# 3_mcu.net
KiCad netlist of a schematic drawn in Altium Designer
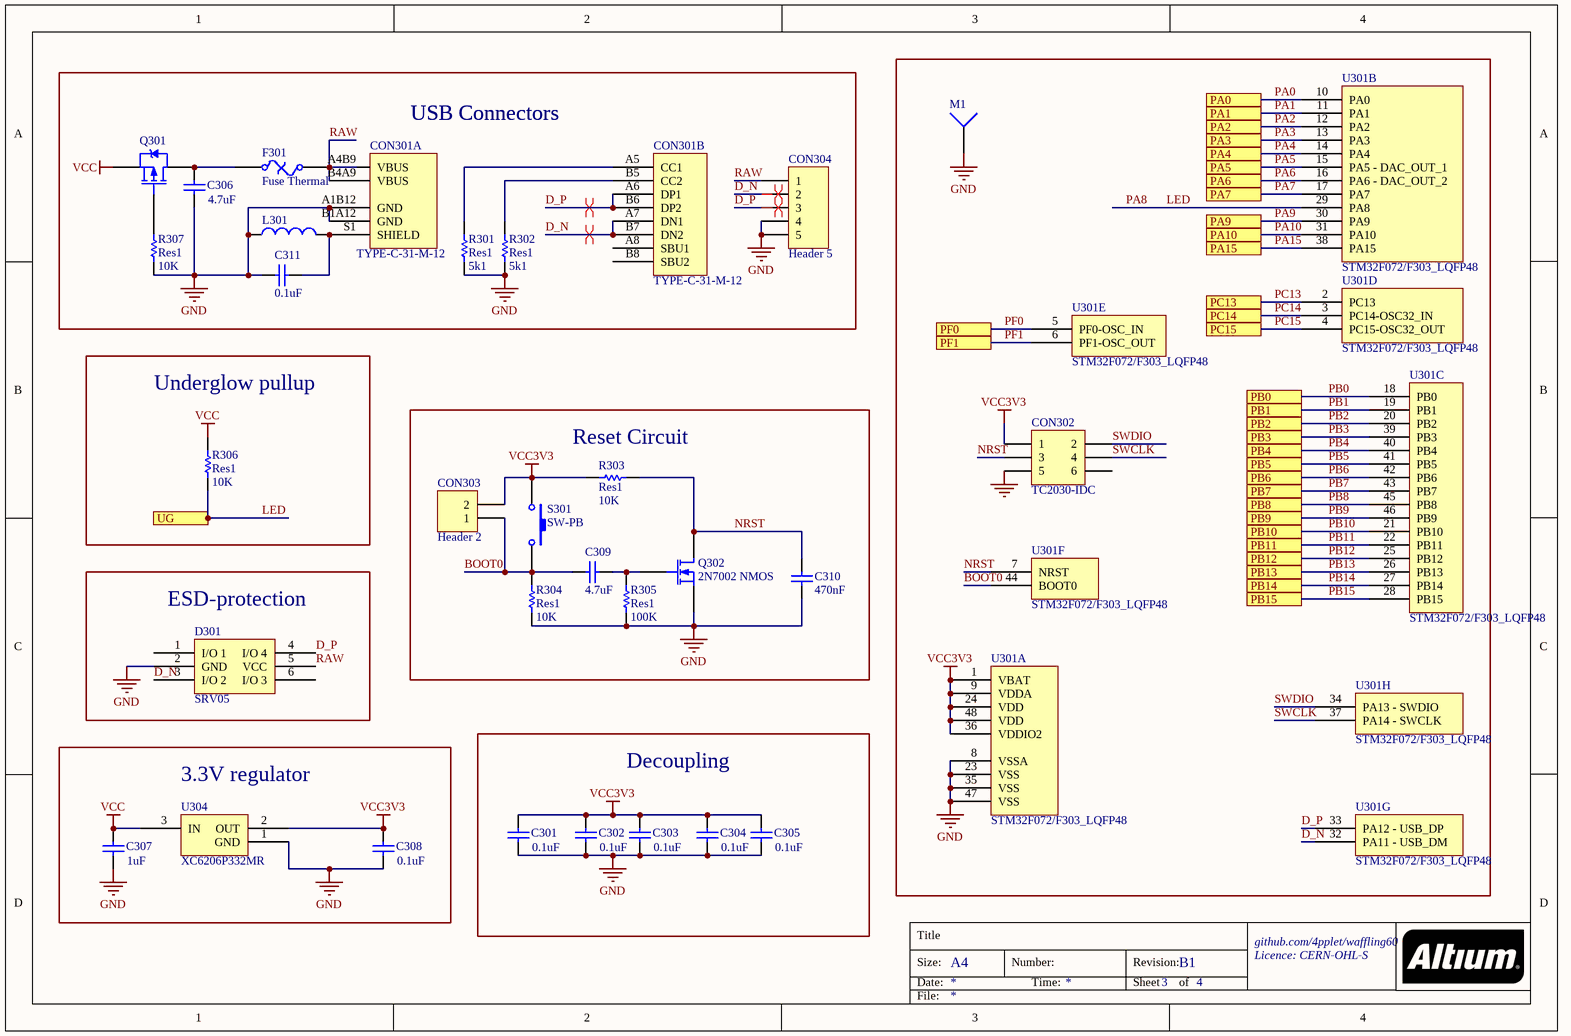
[diagram p0: 3_mcu.SchDoc]

(export (version "E")
  (design (tool "Eeschema 10.0.6"))
  (components
    (comp (ref "C301")
      (value "0.1uF")
      (footprint "C0603[1608]")
      (description "Capacitor")
      (fields (field (name "LCSC PART #") "C14663") (field (name "MRF.PART") "CC0603KRX7R9BB104"))
      (libsource (lib "Miscellaneous Devices") (part "Cap"))
    )
    (comp (ref "C302")
      (value "0.1uF")
      (footprint "C0603[1608]")
      (description "Capacitor")
      (fields (field (name "LCSC PART #") "C14663") (field (name "MRF.PART") "CC0603KRX7R9BB104"))
      (libsource (lib "Miscellaneous Devices") (part "Cap"))
    )
    (comp (ref "C303")
      (value "0.1uF")
      (footprint "C0603[1608]")
      (description "Capacitor")
      (fields (field (name "LCSC PART #") "C14663") (field (name "MRF.PART") "CC0603KRX7R9BB104"))
      (libsource (lib "Miscellaneous Devices") (part "Cap"))
    )
    (comp (ref "C304")
      (value "0.1uF")
      (footprint "C0603[1608]")
      (description "Capacitor")
      (fields (field (name "LCSC PART #") "C14663") (field (name "MRF.PART") "CC0603KRX7R9BB104"))
      (libsource (lib "Miscellaneous Devices") (part "Cap"))
    )
    (comp (ref "C305")
      (value "0.1uF")
      (footprint "C0603[1608]")
      (description "Capacitor")
      (fields (field (name "LCSC PART #") "C14663") (field (name "MRF.PART") "CC0603KRX7R9BB104"))
      (libsource (lib "Miscellaneous Devices") (part "Cap"))
    )
    (comp (ref "C306")
      (value "4.7uF")
      (footprint "C0603[1608]")
      (description "Capacitor")
      (fields (field (name "LCSC PART #") "C19666") (field (name "MRF.PART") "CL10A475KO8NNNC"))
      (libsource (lib "Miscellaneous Devices") (part "Cap"))
    )
    (comp (ref "C307")
      (value "1uF")
      (footprint "C0603[1608]")
      (description "Capacitor")
      (fields (field (name "LCSC PART #") "C15849") (field (name "MRF.PART") "CL10A105KB8NNNC"))
      (libsource (lib "Miscellaneous Devices") (part "Cap"))
    )
    (comp (ref "C308")
      (value "0.1uF")
      (footprint "C0603[1608]")
      (description "Capacitor")
      (fields (field (name "LCSC PART #") "C14663") (field (name "MRF.PART") "CC0603KRX7R9BB104"))
      (libsource (lib "Miscellaneous Devices") (part "Cap"))
    )
    (comp (ref "C309")
      (value "4.7uF")
      (footprint "C0603[1608]")
      (description "Capacitor")
      (fields (field (name "LCSC PART #") "C19666") (field (name "MRF.PART") "CL10A475KO8NNNC"))
      (libsource (lib "Miscellaneous Devices") (part "Cap"))
    )
    (comp (ref "C310")
      (value "470nF")
      (footprint "C0603[1608]")
      (description "Capacitor")
      (fields (field (name "LCSC PART #") "C1623") (field (name "MRF.PART") "CL10B474KA8NNNC"))
      (libsource (lib "Miscellaneous Devices") (part "Cap"))
    )
    (comp (ref "C311")
      (value "0.1uF")
      (footprint "C0603[1608]")
      (description "Capacitor")
      (fields (field (name "LCSC PART #") "C14663") (field (name "MRF.PART") "CC0603KRX7R9BB104"))
      (libsource (lib "Miscellaneous Devices") (part "Cap"))
    )
    (comp (ref "CON301")
      (value "TYPE-C-31-M-12")
      (footprint "TYPE-C-31-M-12")
      (fields (field (name "LCSC PART #") "C165948"))
      (libsource (lib "Schlib1") (part "TYPE-C-31-M-12"))
    )
    (comp (ref "CON302")
      (value "TC2030-IDC")
      (footprint "TC2030-IDC-NL")
      (description "Header, 3-Pin, Dual row")
      (libsource (lib "Miscellaneous Connectors") (part "Header 3X2"))
    )
    (comp (ref "CON303")
      (value "Header 2")
      (footprint "HDR1X2")
      (description "Header, 2-Pin")
      (libsource (lib "Miscellaneous Connectors") (part "Header 2"))
    )
    (comp (ref "CON304")
      (value "Header 5")
      (footprint "JST SM04B-SRSS-TB")
      (description "JST for USB daughter board")
      (fields (field (name "LCSC PART #") "C160404") (field (name "MRF.PART") "SM04B-SRSS-TB(LF)(SN)"))
      (libsource (lib "Miscellaneous Connectors") (part "Header 5"))
    )
    (comp (ref "D301")
      (value "SRV05")
      (footprint "SOT-23-6")
      (fields (field (name "LCSC PART #") "C85364") (field (name "MRF.PART") "SRV05-4-P-T7"))
      (libsource (lib "Keebs") (part "SRV05"))
    )
    (comp (ref "F301")
      (value "Fuse Thermal")
      (footprint "C1206[3216]")
      (description "Thermal Fuse")
      (fields (field (name "LCSC PART #") "C135338") (field (name "MRF.PART") "ASMD1206-050"))
      (libsource (lib "Miscellaneous Devices") (part "Fuse Thermal"))
    )
    (comp (ref "L301")
      (value "Inductor")
      (footprint "L0805")
      (fields (field (name "LCSC PART #") "C1015") (field (name "MRF.PART") "GZ2012D101TF"))
      (libsource (lib "Simulation Generic Components") (part "Inductor"))
    )
    (comp (ref "M1")
      (value "Socket")
      (footprint "mounting_hole")
      (libsource (lib "Miscellaneous Connectors") (part "Socket"))
    )
    (comp (ref "Q301")
      (value "PMOS-2")
      (footprint "SOT-23-3")
      (description "P-Channel Power MOSFET")
      (fields (field (name "LCSC PART #") "C10487") (field (name "MRF.PART") "SI2301CDS-T1-GE3"))
      (libsource (lib "Miscellaneous Devices") (part "PMOS-2"))
    )
    (comp (ref "Q302")
      (value "2N7002 NMOS")
      (footprint "SOT-23-3")
      (description "N-Channel MOSFET")
      (fields (field (name "LCSC PART #") "C8545") (field (name "MRF.PART") "2N7002"))
      (libsource (lib "Miscellaneous Devices") (part "MOSFET-N"))
    )
    (comp (ref "R301")
      (value "Res1")
      (footprint "R0603[1608]")
      (description "Resistor")
      (fields
        (field (name "ALTIUM_VALUE") "5k1")
        (field (name "LCSC PART #") "C23186")
        (field (name "MRF.PART") "0603WAF5101T5E")
      )
      (libsource (lib "Miscellaneous Devices") (part "Res1"))
    )
    (comp (ref "R302")
      (value "Res1")
      (footprint "R0603[1608]")
      (description "Resistor")
      (fields
        (field (name "ALTIUM_VALUE") "5k1")
        (field (name "LCSC PART #") "C23186")
        (field (name "MRF.PART") "0603WAF5101T5E")
      )
      (libsource (lib "Miscellaneous Devices") (part "Res1"))
    )
    (comp (ref "R303")
      (value "Res1")
      (footprint "R0603[1608]")
      (description "Resistor")
      (fields
        (field (name "ALTIUM_VALUE") "10K")
        (field (name "LCSC PART #") "C25804")
        (field (name "MRF.PART") "0603WAF1002T5E")
      )
      (libsource (lib "Miscellaneous Devices") (part "Res1"))
    )
    (comp (ref "R304")
      (value "Res1")
      (footprint "R0603[1608]")
      (description "Resistor")
      (fields
        (field (name "ALTIUM_VALUE") "10K")
        (field (name "LCSC PART #") "C25804")
        (field (name "MRF.PART") "0603WAF1002T5E")
      )
      (libsource (lib "Miscellaneous Devices") (part "Res1"))
    )
    (comp (ref "R305")
      (value "Res1")
      (footprint "R0603[1608]")
      (description "Resistor")
      (fields
        (field (name "ALTIUM_VALUE") "100K")
        (field (name "LCSC PART #") "C25803")
        (field (name "MRF.PART") "0603WAF1003T5E")
      )
      (libsource (lib "Miscellaneous Devices") (part "Res1"))
    )
    (comp (ref "R306")
      (value "Res1")
      (footprint "R0603[1608]")
      (description "Resistor")
      (fields
        (field (name "ALTIUM_VALUE") "10K")
        (field (name "LCSC PART #") "C25804")
        (field (name "MRF.PART") "0603WAF1002T5E")
      )
      (libsource (lib "Miscellaneous Devices") (part "Res1"))
    )
    (comp (ref "R307")
      (value "Res1")
      (footprint "R0603[1608]")
      (description "Resistor")
      (fields
        (field (name "ALTIUM_VALUE") "10K")
        (field (name "LCSC PART #") "C25804")
        (field (name "MRF.PART") "0603WAF1002T5E")
      )
      (libsource (lib "Miscellaneous Devices") (part "Res1"))
    )
    (comp (ref "S301")
      (value "SW-PB")
      (footprint "XKB Switch")
      (description "Switch")
      (fields (field (name "MRF.PART") "TS-1187A-C-D-B") (field (name "LCSC PART #") "C318888"))
      (libsource (lib "Miscellaneous Devices") (part "SW-PB"))
    )
    (comp (ref "U301")
      (value "STM32F072/F303_LQFP48")
      (footprint "STM32 - COMBO 7X7MM")
      (fields (field (name "LCSC PART #") "C915660") (field (name "MRF.PART") "APM32F072CBT6"))
      (libsource (lib "") (part "STM32F072/F303_LQFP48_1"))
    )
    (comp (ref "U304")
      (value "XC6206P332MR")
      (footprint "SOT-23-3")
      (fields (field (name "LCSC PART #") "C5446"))
      (libsource (lib "Keebs") (part "SOT23 LDO"))
    )
  )
  (nets
    (net (code "1") (name "/BOOT0") (class "Default")
      (node (ref "C309") (pin "1") (pinfunction "1_1") (pintype "passive"))
      (node (ref "CON303") (pin "1") (pinfunction "1_1") (pintype "passive"))
      (node (ref "R304") (pin "1") (pinfunction "1_1") (pintype "passive"))
      (node (ref "S301") (pin "2") (pinfunction "2_2") (pintype "passive"))
      (node (ref "U301") (pin "44") (pinfunction "BOOT0_44") (pintype "passive"))
    )
    (net (code "2") (name "/D_N") (class "Default")
      (node (ref "CON301") (pin "A7") (pinfunction "DN1_A7") (pintype "passive"))
      (node (ref "CON301") (pin "B7") (pinfunction "DN2_B7") (pintype "passive"))
      (node (ref "CON304") (pin "2") (pinfunction "2_2") (pintype "passive"))
      (node (ref "D301") (pin "3") (pinfunction "I/O_2_3") (pintype "passive"))
      (node (ref "U301") (pin "32") (pinfunction "PA11_-_USB_DM_32") (pintype "passive"))
    )
    (net (code "3") (name "/D_P") (class "Default")
      (node (ref "CON301") (pin "A6") (pinfunction "DP1_A6") (pintype "passive"))
      (node (ref "CON301") (pin "B6") (pinfunction "DP2_B6") (pintype "passive"))
      (node (ref "CON304") (pin "3") (pinfunction "3_3") (pintype "passive"))
      (node (ref "D301") (pin "4") (pinfunction "I/O_4_4") (pintype "passive"))
      (node (ref "U301") (pin "33") (pinfunction "PA12_-_USB_DP_33") (pintype "passive"))
    )
    (net (code "4") (name "/LED") (class "Default")
      (node (ref "R306") (pin "2") (pinfunction "2_2") (pintype "passive"))
      (node (ref "U301") (pin "29") (pinfunction "PA8_29") (pintype "passive"))
    )
    (net (code "5") (name "/NRST") (class "Default")
      (node (ref "C310") (pin "1") (pinfunction "1_1") (pintype "passive"))
      (node (ref "CON302") (pin "3") (pinfunction "3_3") (pintype "passive"))
      (node (ref "Q302") (pin "3") (pinfunction "D_3") (pintype "passive"))
      (node (ref "R303") (pin "2") (pinfunction "2_2") (pintype "passive"))
      (node (ref "U301") (pin "7") (pinfunction "NRST_7") (pintype "passive"))
    )
    (net (code "6") (name "/PA0") (class "Default")
      (node (ref "U301") (pin "10") (pinfunction "PA0_10") (pintype "passive"))
    )
    (net (code "7") (name "/PA1") (class "Default")
      (node (ref "U301") (pin "11") (pinfunction "PA1_11") (pintype "passive"))
    )
    (net (code "8") (name "/PA2") (class "Default")
      (node (ref "U301") (pin "12") (pinfunction "PA2_12") (pintype "passive"))
    )
    (net (code "9") (name "/PA3") (class "Default")
      (node (ref "U301") (pin "13") (pinfunction "PA3_13") (pintype "passive"))
    )
    (net (code "10") (name "/PA4") (class "Default")
      (node (ref "U301") (pin "14") (pinfunction "PA4_14") (pintype "passive"))
    )
    (net (code "11") (name "/PA5") (class "Default")
      (node (ref "U301") (pin "15") (pinfunction "PA5_-_DAC_OUT_1_15") (pintype "passive"))
    )
    (net (code "12") (name "/PA6") (class "Default")
      (node (ref "U301") (pin "16") (pinfunction "PA6_-_DAC_OUT_2_16") (pintype "passive"))
    )
    (net (code "13") (name "/PA7") (class "Default")
      (node (ref "U301") (pin "17") (pinfunction "PA7_17") (pintype "passive"))
    )
    (net (code "14") (name "/PA9") (class "Default")
      (node (ref "U301") (pin "30") (pinfunction "PA9_30") (pintype "passive"))
    )
    (net (code "15") (name "/PA10") (class "Default")
      (node (ref "U301") (pin "31") (pinfunction "PA10_31") (pintype "passive"))
    )
    (net (code "16") (name "/PA15") (class "Default")
      (node (ref "U301") (pin "38") (pinfunction "PA15_38") (pintype "passive"))
    )
    (net (code "17") (name "/PB0") (class "Default")
      (node (ref "U301") (pin "18") (pinfunction "PB0_18") (pintype "passive"))
    )
    (net (code "18") (name "/PB1") (class "Default")
      (node (ref "U301") (pin "19") (pinfunction "PB1_19") (pintype "passive"))
    )
    (net (code "19") (name "/PB2") (class "Default")
      (node (ref "U301") (pin "20") (pinfunction "PB2_20") (pintype "passive"))
    )
    (net (code "20") (name "/PB3") (class "Default")
      (node (ref "U301") (pin "39") (pinfunction "PB3_39") (pintype "passive"))
    )
    (net (code "21") (name "/PB4") (class "Default")
      (node (ref "U301") (pin "40") (pinfunction "PB4_40") (pintype "passive"))
    )
    (net (code "22") (name "/PB5") (class "Default")
      (node (ref "U301") (pin "41") (pinfunction "PB5_41") (pintype "passive"))
    )
    (net (code "23") (name "/PB6") (class "Default")
      (node (ref "U301") (pin "42") (pinfunction "PB6_42") (pintype "passive"))
    )
    (net (code "24") (name "/PB7") (class "Default")
      (node (ref "U301") (pin "43") (pinfunction "PB7_43") (pintype "passive"))
    )
    (net (code "25") (name "/PB8") (class "Default")
      (node (ref "U301") (pin "45") (pinfunction "PB8_45") (pintype "passive"))
    )
    (net (code "26") (name "/PB9") (class "Default")
      (node (ref "U301") (pin "46") (pinfunction "PB9_46") (pintype "passive"))
    )
    (net (code "27") (name "/PB10") (class "Default")
      (node (ref "U301") (pin "21") (pinfunction "PB10_21") (pintype "passive"))
    )
    (net (code "28") (name "/PB11") (class "Default")
      (node (ref "U301") (pin "22") (pinfunction "PB11_22") (pintype "passive"))
    )
    (net (code "29") (name "/PB12") (class "Default")
      (node (ref "U301") (pin "25") (pinfunction "PB12_25") (pintype "passive"))
    )
    (net (code "30") (name "/PB13") (class "Default")
      (node (ref "U301") (pin "26") (pinfunction "PB13_26") (pintype "passive"))
    )
    (net (code "31") (name "/PB14") (class "Default")
      (node (ref "U301") (pin "27") (pinfunction "PB14_27") (pintype "passive"))
    )
    (net (code "32") (name "/PB15") (class "Default")
      (node (ref "U301") (pin "28") (pinfunction "PB15_28") (pintype "passive"))
    )
    (net (code "33") (name "/PC13") (class "Default")
      (node (ref "U301") (pin "2") (pinfunction "PC13_2") (pintype "passive"))
    )
    (net (code "34") (name "/PC14") (class "Default")
      (node (ref "U301") (pin "3") (pinfunction "PC14-OSC32_IN_3") (pintype "passive"))
    )
    (net (code "35") (name "/PC15") (class "Default")
      (node (ref "U301") (pin "4") (pinfunction "PC15-OSC32_OUT_4") (pintype "passive"))
    )
    (net (code "36") (name "/PF0") (class "Default")
      (node (ref "U301") (pin "5") (pinfunction "PF0-OSC_IN_5") (pintype "passive"))
    )
    (net (code "37") (name "/PF1") (class "Default")
      (node (ref "U301") (pin "6") (pinfunction "PF1-OSC_OUT_6") (pintype "passive"))
    )
    (net (code "38") (name "/RAW") (class "Default")
      (node (ref "CON301") (pin "A4B9") (pinfunction "VBUS_A4B9") (pintype "passive"))
      (node (ref "CON301") (pin "B4A9") (pinfunction "VBUS_B4A9") (pintype "passive"))
      (node (ref "CON304") (pin "1") (pinfunction "1_1") (pintype "passive"))
      (node (ref "D301") (pin "5") (pinfunction "VCC_5") (pintype "passive"))
      (node (ref "F301") (pin "2") (pinfunction "2_2") (pintype "passive"))
    )
    (net (code "39") (name "/SWCLK") (class "Default")
      (node (ref "CON302") (pin "4") (pinfunction "4_4") (pintype "passive"))
      (node (ref "U301") (pin "37") (pinfunction "PA14_-_SWCLK_37") (pintype "passive"))
    )
    (net (code "40") (name "/SWDIO") (class "Default")
      (node (ref "CON302") (pin "2") (pinfunction "2_2") (pintype "passive"))
      (node (ref "U301") (pin "34") (pinfunction "PA13_-_SWDIO_34") (pintype "passive"))
    )
    (net (code "41") (name "GND") (class "Default")
      (node (ref "C301") (pin "1") (pinfunction "1_1") (pintype "passive"))
      (node (ref "C302") (pin "1") (pinfunction "1_1") (pintype "passive"))
      (node (ref "C303") (pin "1") (pinfunction "1_1") (pintype "passive"))
      (node (ref "C304") (pin "1") (pinfunction "1_1") (pintype "passive"))
      (node (ref "C305") (pin "1") (pinfunction "1_1") (pintype "passive"))
      (node (ref "C306") (pin "1") (pinfunction "1_1") (pintype "passive"))
      (node (ref "C307") (pin "1") (pinfunction "1_1") (pintype "passive"))
      (node (ref "C308") (pin "1") (pinfunction "1_1") (pintype "passive"))
      (node (ref "C310") (pin "2") (pinfunction "2_2") (pintype "passive"))
      (node (ref "C311") (pin "1") (pinfunction "1_1") (pintype "passive"))
      (node (ref "CON301") (pin "A1B12") (pinfunction "GND_A1B12") (pintype "passive"))
      (node (ref "CON301") (pin "B1A12") (pinfunction "GND_B1A12") (pintype "passive"))
      (node (ref "CON302") (pin "5") (pinfunction "5_5") (pintype "passive"))
      (node (ref "CON304") (pin "4") (pinfunction "4_4") (pintype "passive"))
      (node (ref "CON304") (pin "5") (pinfunction "5_5") (pintype "passive"))
      (node (ref "D301") (pin "2") (pinfunction "GND_2") (pintype "passive"))
      (node (ref "L301") (pin "1") (pinfunction "1_1") (pintype "passive"))
      (node (ref "M1") (pin "1") (pinfunction "1_1") (pintype "passive"))
      (node (ref "Q302") (pin "2") (pinfunction "S_2") (pintype "passive"))
      (node (ref "R301") (pin "2") (pinfunction "2_2") (pintype "passive"))
      (node (ref "R302") (pin "2") (pinfunction "2_2") (pintype "passive"))
      (node (ref "R304") (pin "2") (pinfunction "2_2") (pintype "passive"))
      (node (ref "R305") (pin "2") (pinfunction "2_2") (pintype "passive"))
      (node (ref "R307") (pin "2") (pinfunction "2_2") (pintype "passive"))
      (node (ref "U301") (pin "23") (pinfunction "VSS_23") (pintype "passive"))
      (node (ref "U301") (pin "35") (pinfunction "VSS_35") (pintype "passive"))
      (node (ref "U301") (pin "47") (pinfunction "VSS_47") (pintype "passive"))
      (node (ref "U301") (pin "8") (pinfunction "VSSA_8") (pintype "passive"))
      (node (ref "U304") (pin "1") (pinfunction "GND_1") (pintype "passive"))
    )
    (net (code "42") (name "Net-(CON301A-SHIELD)") (class "Default")
      (node (ref "C311") (pin "2") (pinfunction "2_2") (pintype "passive"))
      (node (ref "CON301") (pin "S1") (pinfunction "SHIELD_S1") (pintype "passive"))
      (node (ref "L301") (pin "2") (pinfunction "2_2") (pintype "passive"))
    )
    (net (code "43") (name "Net-(CON301B-CC1)") (class "Default")
      (node (ref "CON301") (pin "A5") (pinfunction "CC1_A5") (pintype "passive"))
      (node (ref "R301") (pin "1") (pinfunction "1_1") (pintype "passive"))
    )
    (net (code "44") (name "Net-(CON301B-CC2)") (class "Default")
      (node (ref "CON301") (pin "B5") (pinfunction "CC2_B5") (pintype "passive"))
      (node (ref "R302") (pin "1") (pinfunction "1_1") (pintype "passive"))
    )
    (net (code "45") (name "Net-(Q301-D)") (class "Default")
      (node (ref "C306") (pin "2") (pinfunction "2_2") (pintype "passive"))
      (node (ref "F301") (pin "1") (pinfunction "1_1") (pintype "passive"))
      (node (ref "Q301") (pin "3") (pinfunction "D_3") (pintype "passive"))
    )
    (net (code "46") (name "Net-(Q301-G)") (class "Default")
      (node (ref "Q301") (pin "1") (pinfunction "G_1") (pintype "passive"))
      (node (ref "R307") (pin "1") (pinfunction "1_1") (pintype "passive"))
    )
    (net (code "47") (name "Net-(Q302-G)") (class "Default")
      (node (ref "C309") (pin "2") (pinfunction "2_2") (pintype "passive"))
      (node (ref "Q302") (pin "1") (pinfunction "G_1") (pintype "passive"))
      (node (ref "R305") (pin "1") (pinfunction "1_1") (pintype "passive"))
    )
    (net (code "48") (name "VCC") (class "Default")
      (node (ref "C307") (pin "2") (pinfunction "2_2") (pintype "passive"))
      (node (ref "Q301") (pin "2") (pinfunction "S_2") (pintype "passive"))
      (node (ref "R306") (pin "1") (pinfunction "1_1") (pintype "passive"))
      (node (ref "U304") (pin "3") (pinfunction "IN_3") (pintype "passive"))
    )
    (net (code "49") (name "VCC3V3") (class "Default")
      (node (ref "C301") (pin "2") (pinfunction "2_2") (pintype "passive"))
      (node (ref "C302") (pin "2") (pinfunction "2_2") (pintype "passive"))
      (node (ref "C303") (pin "2") (pinfunction "2_2") (pintype "passive"))
      (node (ref "C304") (pin "2") (pinfunction "2_2") (pintype "passive"))
      (node (ref "C305") (pin "2") (pinfunction "2_2") (pintype "passive"))
      (node (ref "C308") (pin "2") (pinfunction "2_2") (pintype "passive"))
      (node (ref "CON302") (pin "1") (pinfunction "1_1") (pintype "passive"))
      (node (ref "CON303") (pin "2") (pinfunction "2_2") (pintype "passive"))
      (node (ref "R303") (pin "1") (pinfunction "1_1") (pintype "passive"))
      (node (ref "S301") (pin "1") (pinfunction "1_1") (pintype "passive"))
      (node (ref "U301") (pin "1") (pinfunction "VBAT_1") (pintype "passive"))
      (node (ref "U301") (pin "24") (pinfunction "VDD_24") (pintype "passive"))
      (node (ref "U301") (pin "36") (pinfunction "VDDIO2_36") (pintype "passive"))
      (node (ref "U301") (pin "48") (pinfunction "VDD_48") (pintype "passive"))
      (node (ref "U301") (pin "9") (pinfunction "VDDA_9") (pintype "passive"))
      (node (ref "U304") (pin "2") (pinfunction "OUT_2") (pintype "passive"))
    )
    (net (code "50") (name "unconnected-(CON301B-SBU1-PadA8)") (class "Default")
      (node (ref "CON301") (pin "A8") (pinfunction "SBU1_A8") (pintype "passive"))
    )
    (net (code "51") (name "unconnected-(CON301B-SBU2-PadB8)") (class "Default")
      (node (ref "CON301") (pin "B8") (pinfunction "SBU2_B8") (pintype "passive"))
    )
    (net (code "52") (name "unconnected-(CON302-Pad6)") (class "Default")
      (node (ref "CON302") (pin "6") (pinfunction "6_6") (pintype "passive"))
    )
    (net (code "53") (name "unconnected-(D301-I{slash}O_1-Pad1)") (class "Default")
      (node (ref "D301") (pin "1") (pinfunction "I/O_1_1") (pintype "passive"))
    )
    (net (code "54") (name "unconnected-(D301-I{slash}O_3-Pad6)") (class "Default")
      (node (ref "D301") (pin "6") (pinfunction "I/O_3_6") (pintype "passive"))
    )
  )
)
